# I2C-LCD-Backpack.net
KiCad netlist of a schematic drawn in EAGLE
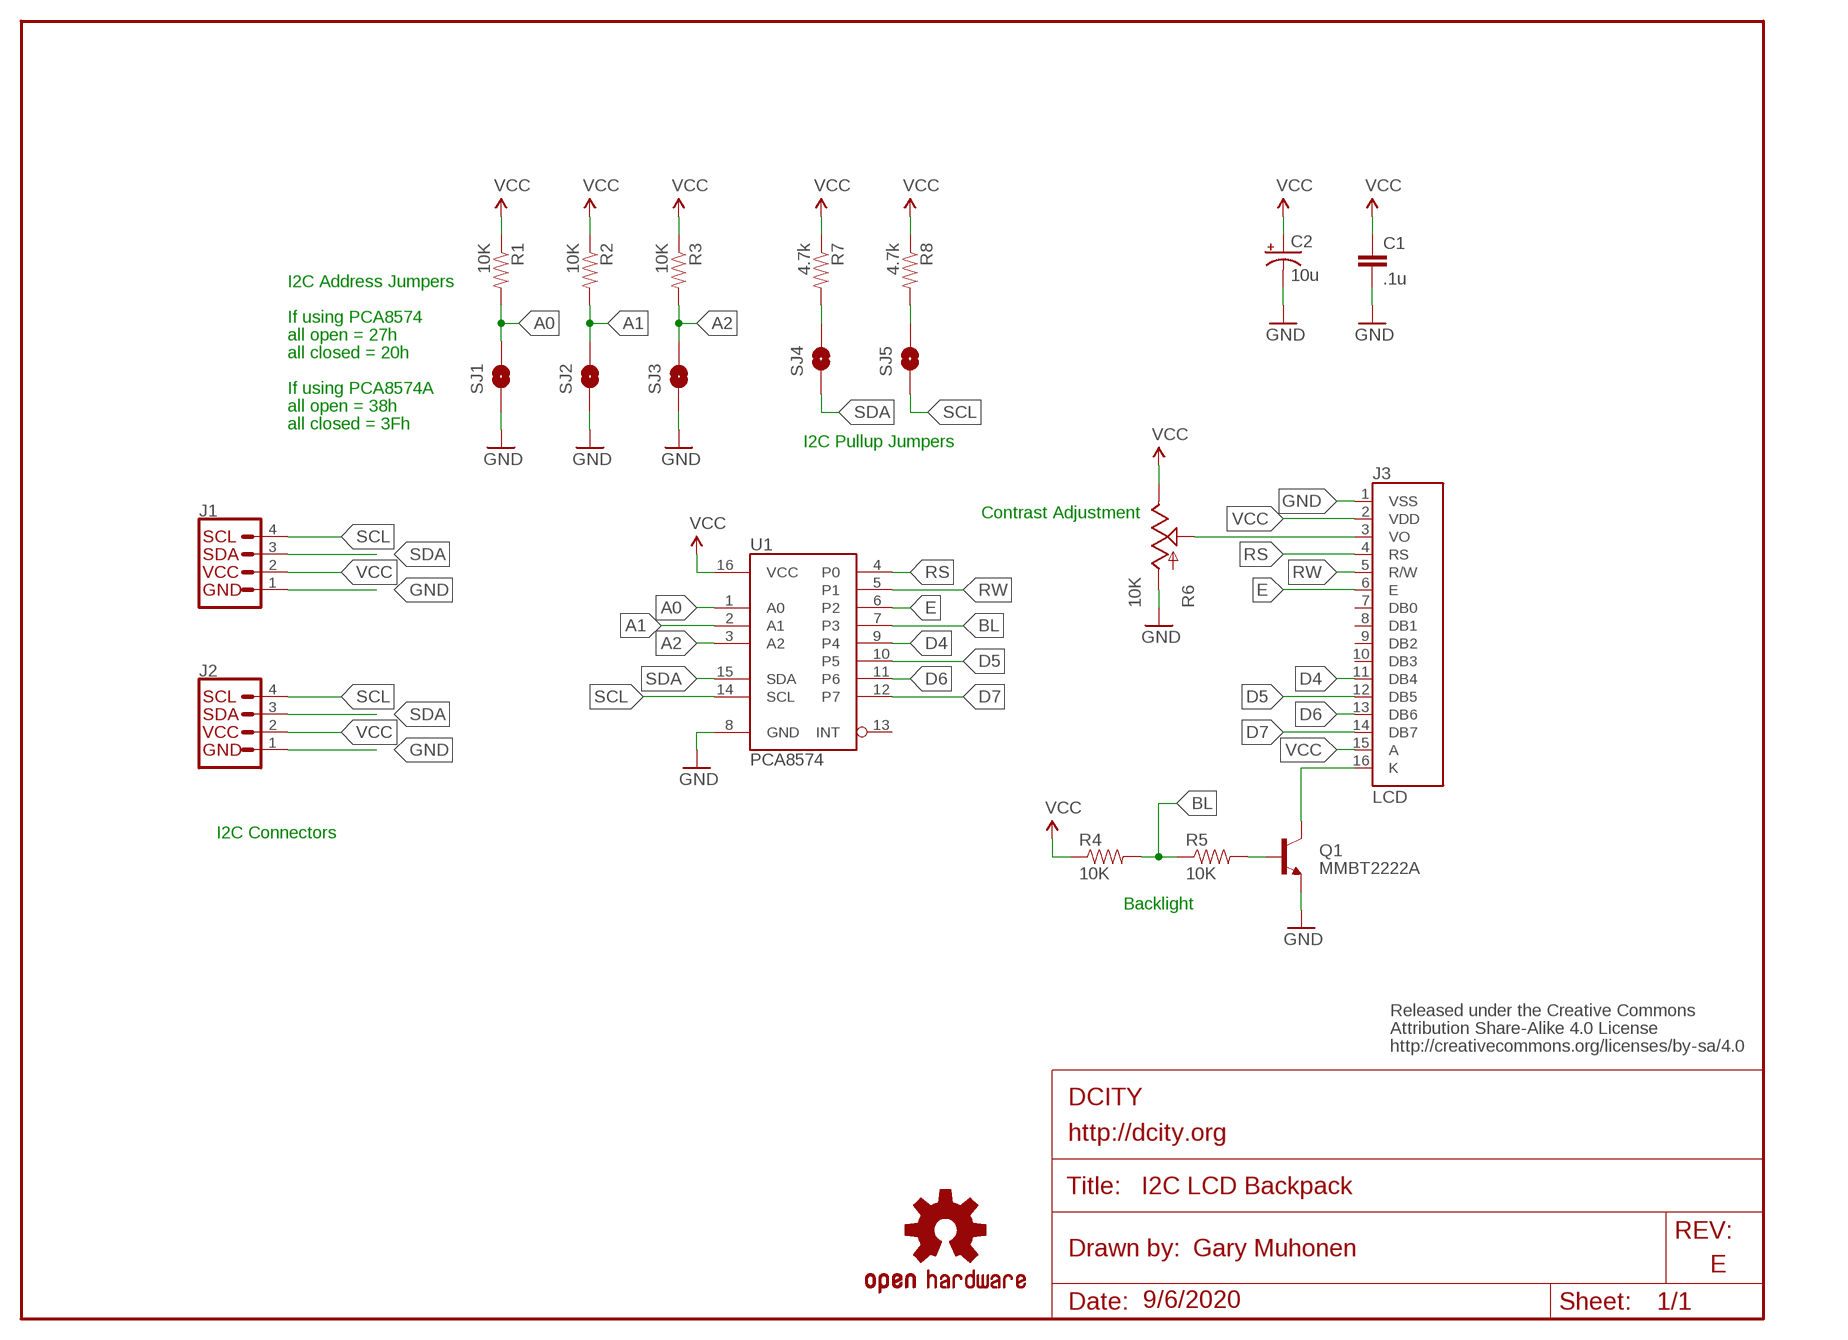
[diagram p0: schematic, sheet 1]

(export (version "E")
  (design (tool "Eeschema 10.0.6"))
  (components
    (comp (ref "C1")
      (value ".1u")
      (footprint "eagle-import:0805-CAP")
      (libsource (lib "eagle-import") (part "CAP0805"))
    )
    (comp (ref "C2")
      (value "10u")
      (footprint "eagle-import:0805-POL")
      (libsource (lib "eagle-import") (part "CAP_POL0805"))
    )
    (comp (ref "J1")
      (value "QWIIC_RIGHT_ANGLE")
      (footprint "eagle-import:JST04_1MM_RA")
      (libsource (lib "eagle-import") (part "QWIIC_CONNECTORJS-1MM"))
    )
    (comp (ref "J2")
      (value "QWIIC_RIGHT_ANGLE")
      (footprint "eagle-import:JST04_1MM_RA")
      (libsource (lib "eagle-import") (part "QWIIC_CONNECTORJS-1MM"))
    )
    (comp (ref "J3")
      (value "LCD")
      (footprint "eagle-import:1X16_LOCK")
      (libsource (lib "eagle-import") (part "LCD-16X2LOCK"))
    )
    (comp (ref "LOGO1")
      (value "OSHW-LOGOS")
      (footprint "eagle-import:OSHW-LOGO-S")
      (libsource (lib "eagle-import") (part "OSHW-LOGOS"))
    )
    (comp (ref "Q1")
      (value "MMBT2222A")
      (footprint "eagle-import:SOT23-3")
      (libsource (lib "eagle-import") (part "TRANSISTOR_NPNMMBT2222A"))
    )
    (comp (ref "R1")
      (value "10K")
      (footprint "eagle-import:0805-RES")
      (libsource (lib "eagle-import") (part "RESISTOR0805"))
    )
    (comp (ref "R2")
      (value "10K")
      (footprint "eagle-import:0805-RES")
      (libsource (lib "eagle-import") (part "RESISTOR0805"))
    )
    (comp (ref "R3")
      (value "10K")
      (footprint "eagle-import:0805-RES")
      (libsource (lib "eagle-import") (part "RESISTOR0805"))
    )
    (comp (ref "R4")
      (value "10K")
      (footprint "eagle-import:0805-RES")
      (libsource (lib "eagle-import") (part "RESISTOR0805"))
    )
    (comp (ref "R5")
      (value "10K")
      (footprint "eagle-import:0805-RES")
      (libsource (lib "eagle-import") (part "RESISTOR0805"))
    )
    (comp (ref "R6")
      (value "10K")
      (footprint "eagle-import:TC33X")
      (libsource (lib "eagle-import") (part "10K_LINEAR_POT_SMD"))
    )
    (comp (ref "R7")
      (value "4.7k")
      (footprint "eagle-import:0805-RES")
      (libsource (lib "eagle-import") (part "RESISTOR0805"))
    )
    (comp (ref "R8")
      (value "4.7k")
      (footprint "eagle-import:0805-RES")
      (libsource (lib "eagle-import") (part "RESISTOR0805"))
    )
    (comp (ref "SJ1")
      (value "SOLDERJUMPERNC")
      (footprint "eagle-import:SJ_2S")
      (libsource (lib "eagle-import") (part "SOLDERJUMPERNC"))
    )
    (comp (ref "SJ2")
      (value "SOLDERJUMPERNC")
      (footprint "eagle-import:SJ_2S")
      (libsource (lib "eagle-import") (part "SOLDERJUMPERNC"))
    )
    (comp (ref "SJ3")
      (value "SOLDERJUMPERNC")
      (footprint "eagle-import:SJ_2S")
      (libsource (lib "eagle-import") (part "SOLDERJUMPERNC"))
    )
    (comp (ref "SJ4")
      (value "SOLDERJUMPERNC")
      (footprint "eagle-import:SJ_2S")
      (libsource (lib "eagle-import") (part "SOLDERJUMPERNC"))
    )
    (comp (ref "SJ5")
      (value "SOLDERJUMPERNC")
      (footprint "eagle-import:SJ_2S")
      (libsource (lib "eagle-import") (part "SOLDERJUMPERNC"))
    )
    (comp (ref "U$2")
      (value "CREATIVE_COMMONS")
      (footprint "eagle-import:CREATIVE_COMMONS")
      (libsource (lib "eagle-import") (part "CREATIVE_COMMONS"))
    )
    (comp (ref "U1")
      (value "PCA8574")
      (footprint "eagle-import:TSSOP16")
      (libsource (lib "eagle-import") (part "PCA8574"))
    )
  )
  (nets
    (net (code "1") (name "A0") (class "Default")
      (node (ref "R1") (pin "2") (pinfunction "2_2") (pintype "passive"))
      (node (ref "SJ1") (pin "2") (pinfunction "2_2") (pintype "passive"))
      (node (ref "U1") (pin "1") (pinfunction "A0_1") (pintype "bidirectional"))
    )
    (net (code "2") (name "A1") (class "Default")
      (node (ref "R2") (pin "2") (pinfunction "2_2") (pintype "passive"))
      (node (ref "SJ2") (pin "2") (pinfunction "2_2") (pintype "passive"))
      (node (ref "U1") (pin "2") (pinfunction "A1_2") (pintype "bidirectional"))
    )
    (net (code "3") (name "A2") (class "Default")
      (node (ref "R3") (pin "2") (pinfunction "2_2") (pintype "passive"))
      (node (ref "SJ3") (pin "2") (pinfunction "2_2") (pintype "passive"))
      (node (ref "U1") (pin "3") (pinfunction "A2_3") (pintype "bidirectional"))
    )
    (net (code "4") (name "BL") (class "Default")
      (node (ref "R4") (pin "2") (pinfunction "2_2") (pintype "passive"))
      (node (ref "R5") (pin "1") (pinfunction "1_1") (pintype "passive"))
      (node (ref "U1") (pin "7") (pinfunction "P3_7") (pintype "bidirectional"))
    )
    (net (code "5") (name "D4") (class "Default")
      (node (ref "J3") (pin "11") (pinfunction "DB4_11") (pintype "bidirectional"))
      (node (ref "U1") (pin "9") (pinfunction "P4_9") (pintype "bidirectional"))
    )
    (net (code "6") (name "D5") (class "Default")
      (node (ref "J3") (pin "12") (pinfunction "DB5_12") (pintype "bidirectional"))
      (node (ref "U1") (pin "10") (pinfunction "P5_10") (pintype "bidirectional"))
    )
    (net (code "7") (name "D6") (class "Default")
      (node (ref "J3") (pin "13") (pinfunction "DB6_13") (pintype "bidirectional"))
      (node (ref "U1") (pin "11") (pinfunction "P6_11") (pintype "bidirectional"))
    )
    (net (code "8") (name "D7") (class "Default")
      (node (ref "J3") (pin "14") (pinfunction "DB7_14") (pintype "bidirectional"))
      (node (ref "U1") (pin "12") (pinfunction "P7_12") (pintype "bidirectional"))
    )
    (net (code "9") (name "E") (class "Default")
      (node (ref "J3") (pin "6") (pinfunction "E_6") (pintype "input"))
      (node (ref "U1") (pin "6") (pinfunction "P2_6") (pintype "bidirectional"))
    )
    (net (code "10") (name "GND") (class "Default")
      (node (ref "C1") (pin "2") (pinfunction "2_2") (pintype "passive"))
      (node (ref "C2") (pin "-") (pinfunction "-_-") (pintype "passive"))
      (node (ref "J1") (pin "1") (pinfunction "1_1") (pintype "power_in"))
      (node (ref "J2") (pin "1") (pinfunction "1_1") (pintype "power_in"))
      (node (ref "J3") (pin "1") (pinfunction "VSS_1") (pintype "power_in"))
      (node (ref "Q1") (pin "2") (pinfunction "E_2") (pintype "passive"))
      (node (ref "R6") (pin "1") (pinfunction "A_1") (pintype "passive"))
      (node (ref "SJ1") (pin "1") (pinfunction "1_1") (pintype "passive"))
      (node (ref "SJ2") (pin "1") (pinfunction "1_1") (pintype "passive"))
      (node (ref "SJ3") (pin "1") (pinfunction "1_1") (pintype "passive"))
      (node (ref "U1") (pin "8") (pinfunction "GND_8") (pintype "bidirectional"))
    )
    (net (code "11") (name "Net-(J3-K)") (class "Default")
      (node (ref "J3") (pin "16") (pinfunction "K_16") (pintype "power_in"))
      (node (ref "Q1") (pin "3") (pinfunction "C_3") (pintype "passive"))
    )
    (net (code "12") (name "Net-(J3-VO)") (class "Default")
      (node (ref "J3") (pin "3") (pinfunction "VO_3") (pintype "bidirectional"))
      (node (ref "R6") (pin "2") (pinfunction "S_2") (pintype "passive"))
    )
    (net (code "13") (name "Net-(Q1-B)") (class "Default")
      (node (ref "Q1") (pin "1") (pinfunction "B_1") (pintype "passive"))
      (node (ref "R5") (pin "2") (pinfunction "2_2") (pintype "passive"))
    )
    (net (code "14") (name "Net-(R7-Pad2)") (class "Default")
      (node (ref "R7") (pin "2") (pinfunction "2_2") (pintype "passive"))
      (node (ref "SJ4") (pin "2") (pinfunction "2_2") (pintype "passive"))
    )
    (net (code "15") (name "Net-(R8-Pad2)") (class "Default")
      (node (ref "R8") (pin "2") (pinfunction "2_2") (pintype "passive"))
      (node (ref "SJ5") (pin "2") (pinfunction "2_2") (pintype "passive"))
    )
    (net (code "16") (name "RS") (class "Default")
      (node (ref "J3") (pin "4") (pinfunction "RS_4") (pintype "input"))
      (node (ref "U1") (pin "4") (pinfunction "P0_4") (pintype "bidirectional"))
    )
    (net (code "17") (name "RW") (class "Default")
      (node (ref "J3") (pin "5") (pinfunction "R/W_5") (pintype "input"))
      (node (ref "U1") (pin "5") (pinfunction "P1_5") (pintype "bidirectional"))
    )
    (net (code "18") (name "SCL") (class "Default")
      (node (ref "J1") (pin "4") (pinfunction "4_4") (pintype "passive"))
      (node (ref "J2") (pin "4") (pinfunction "4_4") (pintype "passive"))
      (node (ref "SJ5") (pin "1") (pinfunction "1_1") (pintype "passive"))
      (node (ref "U1") (pin "14") (pinfunction "SCL_14") (pintype "bidirectional"))
    )
    (net (code "19") (name "SDA") (class "Default")
      (node (ref "J1") (pin "3") (pinfunction "3_3") (pintype "passive"))
      (node (ref "J2") (pin "3") (pinfunction "3_3") (pintype "passive"))
      (node (ref "SJ4") (pin "1") (pinfunction "1_1") (pintype "passive"))
      (node (ref "U1") (pin "15") (pinfunction "SDA_15") (pintype "bidirectional"))
    )
    (net (code "20") (name "VCC") (class "Default")
      (node (ref "C1") (pin "1") (pinfunction "1_1") (pintype "passive"))
      (node (ref "C2") (pin "+") (pinfunction "+_+") (pintype "passive"))
      (node (ref "J1") (pin "2") (pinfunction "2_2") (pintype "power_in"))
      (node (ref "J2") (pin "2") (pinfunction "2_2") (pintype "power_in"))
      (node (ref "J3") (pin "15") (pinfunction "A_15") (pintype "power_in"))
      (node (ref "J3") (pin "2") (pinfunction "VDD_2") (pintype "power_in"))
      (node (ref "R1") (pin "1") (pinfunction "1_1") (pintype "passive"))
      (node (ref "R2") (pin "1") (pinfunction "1_1") (pintype "passive"))
      (node (ref "R3") (pin "1") (pinfunction "1_1") (pintype "passive"))
      (node (ref "R4") (pin "1") (pinfunction "1_1") (pintype "passive"))
      (node (ref "R6") (pin "3") (pinfunction "E_3") (pintype "passive"))
      (node (ref "R7") (pin "1") (pinfunction "1_1") (pintype "passive"))
      (node (ref "R8") (pin "1") (pinfunction "1_1") (pintype "passive"))
      (node (ref "U1") (pin "16") (pinfunction "VCC_16") (pintype "bidirectional"))
    )
    (net (code "21") (name "unconnected-(J3-DB0-Pad7)") (class "Default")
      (node (ref "J3") (pin "7") (pinfunction "DB0_7") (pintype "bidirectional"))
    )
    (net (code "22") (name "unconnected-(J3-DB1-Pad8)") (class "Default")
      (node (ref "J3") (pin "8") (pinfunction "DB1_8") (pintype "bidirectional"))
    )
    (net (code "23") (name "unconnected-(J3-DB2-Pad9)") (class "Default")
      (node (ref "J3") (pin "9") (pinfunction "DB2_9") (pintype "bidirectional"))
    )
    (net (code "24") (name "unconnected-(J3-DB3-Pad10)") (class "Default")
      (node (ref "J3") (pin "10") (pinfunction "DB3_10") (pintype "bidirectional"))
    )
    (net (code "25") (name "unconnected-(U1-INT-Pad13)") (class "Default")
      (node (ref "U1") (pin "13") (pinfunction "INT_13") (pintype "output"))
    )
  )
)
